# Keypad.net
KiCad netlist of a schematic drawn in EAGLE
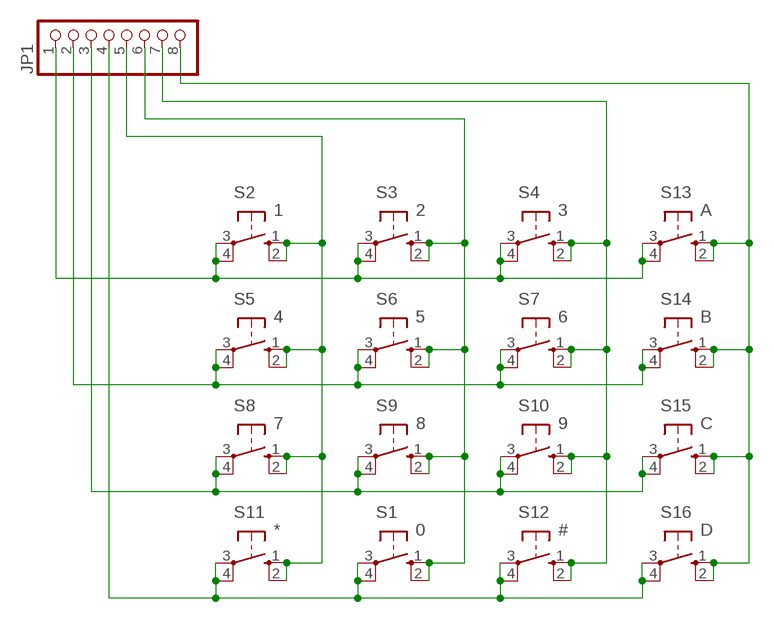
[diagram p0: schematic, sheet 1]

(export (version "E")
  (design (tool "Eeschema 10.0.6"))
  (components
    (comp (ref "JP1")
      (value "PINHD-1X8")
      (footprint "eagle-import:1X08")
      (libsource (lib "eagle-import") (part "PINHD-1X8"))
    )
    (comp (ref "S1")
      (value "0")
      (footprint "eagle-import:B3F-10XX")
      (fields (field (name "MPN") "B3F-1000"))
      (libsource (lib "eagle-import") (part "10-XX"))
    )
    (comp (ref "S2")
      (value "1")
      (footprint "eagle-import:B3F-10XX")
      (fields (field (name "MPN") "B3F-1000"))
      (libsource (lib "eagle-import") (part "10-XX"))
    )
    (comp (ref "S3")
      (value "2")
      (footprint "eagle-import:B3F-10XX")
      (fields (field (name "MPN") "B3F-1000"))
      (libsource (lib "eagle-import") (part "10-XX"))
    )
    (comp (ref "S4")
      (value "3")
      (footprint "eagle-import:B3F-10XX")
      (fields (field (name "MPN") "B3F-1000"))
      (libsource (lib "eagle-import") (part "10-XX"))
    )
    (comp (ref "S5")
      (value "4")
      (footprint "eagle-import:B3F-10XX")
      (fields (field (name "MPN") "B3F-1000"))
      (libsource (lib "eagle-import") (part "10-XX"))
    )
    (comp (ref "S6")
      (value "5")
      (footprint "eagle-import:B3F-10XX")
      (fields (field (name "MPN") "B3F-1000"))
      (libsource (lib "eagle-import") (part "10-XX"))
    )
    (comp (ref "S7")
      (value "6")
      (footprint "eagle-import:B3F-10XX")
      (fields (field (name "MPN") "B3F-1000"))
      (libsource (lib "eagle-import") (part "10-XX"))
    )
    (comp (ref "S8")
      (value "7")
      (footprint "eagle-import:B3F-10XX")
      (fields (field (name "MPN") "B3F-1000"))
      (libsource (lib "eagle-import") (part "10-XX"))
    )
    (comp (ref "S9")
      (value "8")
      (footprint "eagle-import:B3F-10XX")
      (fields (field (name "MPN") "B3F-1000"))
      (libsource (lib "eagle-import") (part "10-XX"))
    )
    (comp (ref "S10")
      (value "9")
      (footprint "eagle-import:B3F-10XX")
      (fields (field (name "MPN") "B3F-1000"))
      (libsource (lib "eagle-import") (part "10-XX"))
    )
    (comp (ref "S11")
      (value "*")
      (footprint "eagle-import:B3F-10XX")
      (fields (field (name "MPN") "B3F-1000"))
      (libsource (lib "eagle-import") (part "10-XX"))
    )
    (comp (ref "S12")
      (value "#")
      (footprint "eagle-import:B3F-10XX")
      (fields (field (name "MPN") "B3F-1000"))
      (libsource (lib "eagle-import") (part "10-XX"))
    )
    (comp (ref "S13")
      (value "A")
      (footprint "eagle-import:B3F-10XX")
      (fields (field (name "MPN") "B3F-1000"))
      (libsource (lib "eagle-import") (part "10-XX"))
    )
    (comp (ref "S14")
      (value "B")
      (footprint "eagle-import:B3F-10XX")
      (fields (field (name "MPN") "B3F-1000"))
      (libsource (lib "eagle-import") (part "10-XX"))
    )
    (comp (ref "S15")
      (value "C")
      (footprint "eagle-import:B3F-10XX")
      (fields (field (name "MPN") "B3F-1000"))
      (libsource (lib "eagle-import") (part "10-XX"))
    )
    (comp (ref "S16")
      (value "D")
      (footprint "eagle-import:B3F-10XX")
      (fields (field (name "MPN") "B3F-1000"))
      (libsource (lib "eagle-import") (part "10-XX"))
    )
  )
  (nets
    (net (code "1") (name "Net-(S1-P)") (class "Default")
      (node (ref "JP1") (pin "4") (pinfunction "4_4") (pintype "passive"))
      (node (ref "S1") (pin "3") (pinfunction "P_3") (pintype "passive"))
      (node (ref "S1") (pin "4") (pinfunction "P1_4") (pintype "passive"))
      (node (ref "S11") (pin "3") (pinfunction "P_3") (pintype "passive"))
      (node (ref "S11") (pin "4") (pinfunction "P1_4") (pintype "passive"))
      (node (ref "S12") (pin "3") (pinfunction "P_3") (pintype "passive"))
      (node (ref "S12") (pin "4") (pinfunction "P1_4") (pintype "passive"))
      (node (ref "S16") (pin "3") (pinfunction "P_3") (pintype "passive"))
      (node (ref "S16") (pin "4") (pinfunction "P1_4") (pintype "passive"))
    )
    (net (code "2") (name "Net-(S1-S)") (class "Default")
      (node (ref "JP1") (pin "6") (pinfunction "6_6") (pintype "passive"))
      (node (ref "S1") (pin "1") (pinfunction "S_1") (pintype "passive"))
      (node (ref "S1") (pin "2") (pinfunction "S1_2") (pintype "passive"))
      (node (ref "S3") (pin "1") (pinfunction "S_1") (pintype "passive"))
      (node (ref "S3") (pin "2") (pinfunction "S1_2") (pintype "passive"))
      (node (ref "S6") (pin "1") (pinfunction "S_1") (pintype "passive"))
      (node (ref "S6") (pin "2") (pinfunction "S1_2") (pintype "passive"))
      (node (ref "S9") (pin "1") (pinfunction "S_1") (pintype "passive"))
      (node (ref "S9") (pin "2") (pinfunction "S1_2") (pintype "passive"))
    )
    (net (code "3") (name "Net-(S10-P)") (class "Default")
      (node (ref "JP1") (pin "3") (pinfunction "3_3") (pintype "passive"))
      (node (ref "S10") (pin "3") (pinfunction "P_3") (pintype "passive"))
      (node (ref "S10") (pin "4") (pinfunction "P1_4") (pintype "passive"))
      (node (ref "S15") (pin "3") (pinfunction "P_3") (pintype "passive"))
      (node (ref "S15") (pin "4") (pinfunction "P1_4") (pintype "passive"))
      (node (ref "S8") (pin "3") (pinfunction "P_3") (pintype "passive"))
      (node (ref "S8") (pin "4") (pinfunction "P1_4") (pintype "passive"))
      (node (ref "S9") (pin "3") (pinfunction "P_3") (pintype "passive"))
      (node (ref "S9") (pin "4") (pinfunction "P1_4") (pintype "passive"))
    )
    (net (code "4") (name "Net-(S10-S)") (class "Default")
      (node (ref "JP1") (pin "7") (pinfunction "7_7") (pintype "passive"))
      (node (ref "S10") (pin "1") (pinfunction "S_1") (pintype "passive"))
      (node (ref "S10") (pin "2") (pinfunction "S1_2") (pintype "passive"))
      (node (ref "S12") (pin "1") (pinfunction "S_1") (pintype "passive"))
      (node (ref "S12") (pin "2") (pinfunction "S1_2") (pintype "passive"))
      (node (ref "S4") (pin "1") (pinfunction "S_1") (pintype "passive"))
      (node (ref "S4") (pin "2") (pinfunction "S1_2") (pintype "passive"))
      (node (ref "S7") (pin "1") (pinfunction "S_1") (pintype "passive"))
      (node (ref "S7") (pin "2") (pinfunction "S1_2") (pintype "passive"))
    )
    (net (code "5") (name "Net-(S11-S)") (class "Default")
      (node (ref "JP1") (pin "5") (pinfunction "5_5") (pintype "passive"))
      (node (ref "S11") (pin "1") (pinfunction "S_1") (pintype "passive"))
      (node (ref "S11") (pin "2") (pinfunction "S1_2") (pintype "passive"))
      (node (ref "S2") (pin "1") (pinfunction "S_1") (pintype "passive"))
      (node (ref "S2") (pin "2") (pinfunction "S1_2") (pintype "passive"))
      (node (ref "S5") (pin "1") (pinfunction "S_1") (pintype "passive"))
      (node (ref "S5") (pin "2") (pinfunction "S1_2") (pintype "passive"))
      (node (ref "S8") (pin "1") (pinfunction "S_1") (pintype "passive"))
      (node (ref "S8") (pin "2") (pinfunction "S1_2") (pintype "passive"))
    )
    (net (code "6") (name "Net-(S13-P)") (class "Default")
      (node (ref "JP1") (pin "1") (pinfunction "1_1") (pintype "passive"))
      (node (ref "S13") (pin "3") (pinfunction "P_3") (pintype "passive"))
      (node (ref "S13") (pin "4") (pinfunction "P1_4") (pintype "passive"))
      (node (ref "S2") (pin "3") (pinfunction "P_3") (pintype "passive"))
      (node (ref "S2") (pin "4") (pinfunction "P1_4") (pintype "passive"))
      (node (ref "S3") (pin "3") (pinfunction "P_3") (pintype "passive"))
      (node (ref "S3") (pin "4") (pinfunction "P1_4") (pintype "passive"))
      (node (ref "S4") (pin "3") (pinfunction "P_3") (pintype "passive"))
      (node (ref "S4") (pin "4") (pinfunction "P1_4") (pintype "passive"))
    )
    (net (code "7") (name "Net-(S13-S)") (class "Default")
      (node (ref "JP1") (pin "8") (pinfunction "8_8") (pintype "passive"))
      (node (ref "S13") (pin "1") (pinfunction "S_1") (pintype "passive"))
      (node (ref "S13") (pin "2") (pinfunction "S1_2") (pintype "passive"))
      (node (ref "S14") (pin "1") (pinfunction "S_1") (pintype "passive"))
      (node (ref "S14") (pin "2") (pinfunction "S1_2") (pintype "passive"))
      (node (ref "S15") (pin "1") (pinfunction "S_1") (pintype "passive"))
      (node (ref "S15") (pin "2") (pinfunction "S1_2") (pintype "passive"))
      (node (ref "S16") (pin "1") (pinfunction "S_1") (pintype "passive"))
      (node (ref "S16") (pin "2") (pinfunction "S1_2") (pintype "passive"))
    )
    (net (code "8") (name "Net-(S14-P)") (class "Default")
      (node (ref "JP1") (pin "2") (pinfunction "2_2") (pintype "passive"))
      (node (ref "S14") (pin "3") (pinfunction "P_3") (pintype "passive"))
      (node (ref "S14") (pin "4") (pinfunction "P1_4") (pintype "passive"))
      (node (ref "S5") (pin "3") (pinfunction "P_3") (pintype "passive"))
      (node (ref "S5") (pin "4") (pinfunction "P1_4") (pintype "passive"))
      (node (ref "S6") (pin "3") (pinfunction "P_3") (pintype "passive"))
      (node (ref "S6") (pin "4") (pinfunction "P1_4") (pintype "passive"))
      (node (ref "S7") (pin "3") (pinfunction "P_3") (pintype "passive"))
      (node (ref "S7") (pin "4") (pinfunction "P1_4") (pintype "passive"))
    )
  )
)
